# Car_Circuitry.net
KiCad netlist of a schematic drawn in Altium Designer
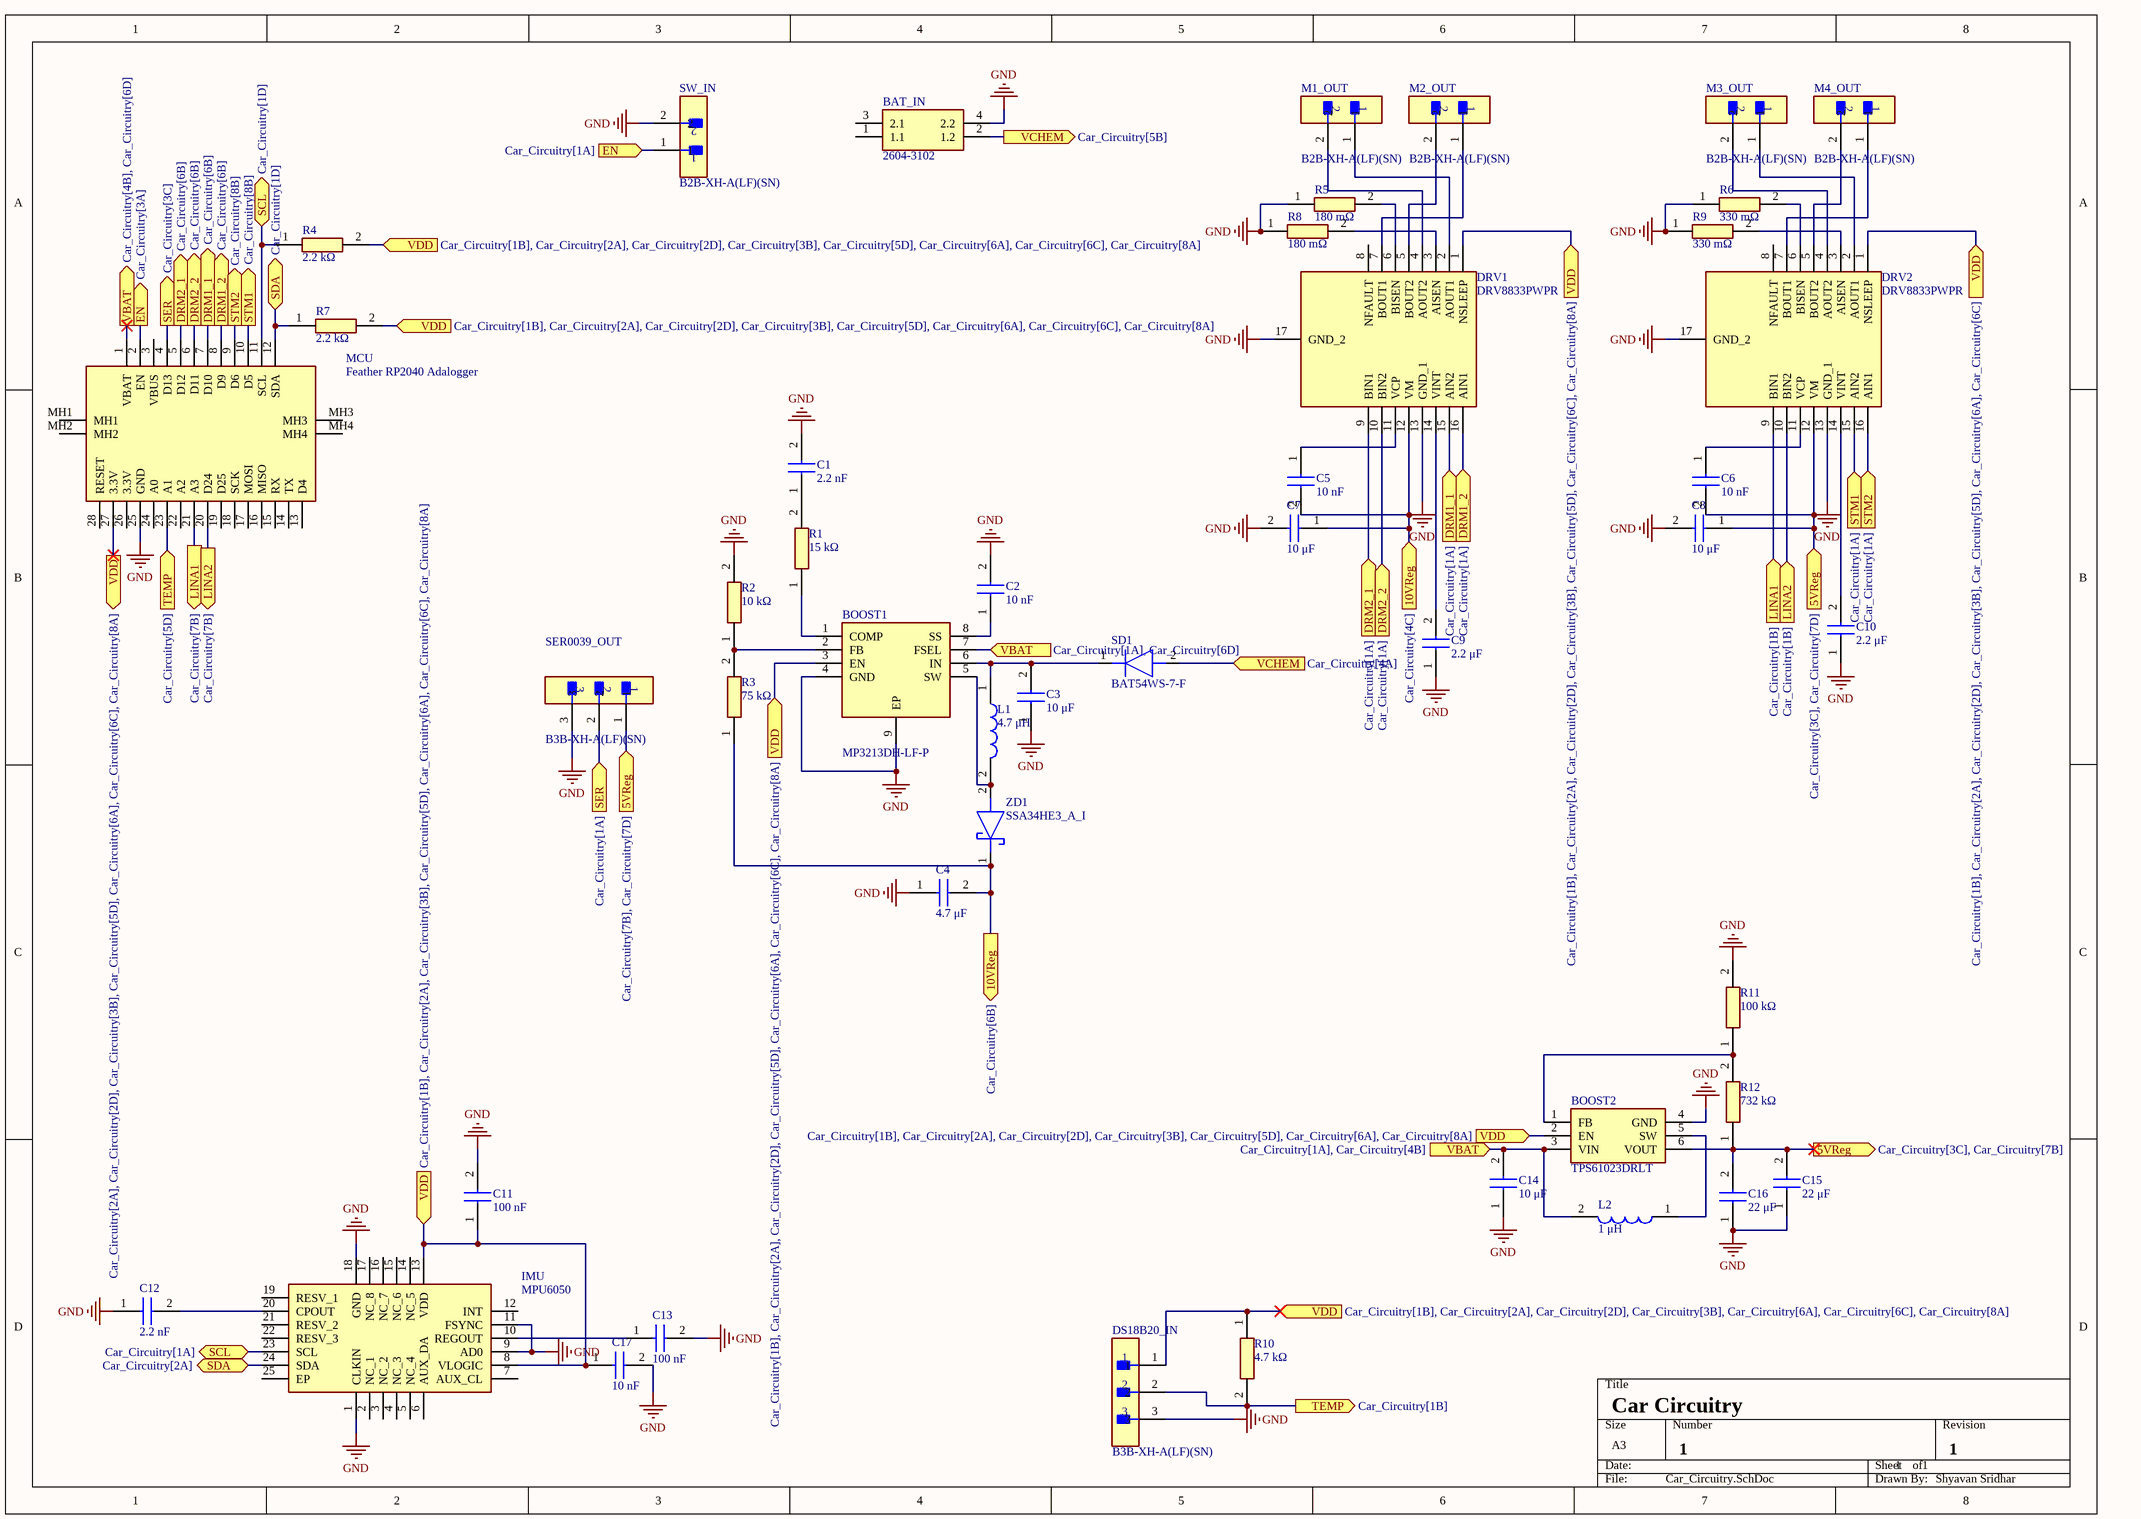
[diagram p0: Car_Circuitry.SchDoc]

(export (version "E")
  (design (tool "Eeschema 10.0.6"))
  (components
    (comp (ref "BAT_IN")
      (value "2604-3102")
      (footprint "SamacSys:26043102")
      (description "Connector")
      (libsource (lib "*") (part "2604-3102"))
    )
    (comp (ref "BOOST1")
      (value "MP3213DH-LF-P")
      (footprint "SamacSys:SOP65P490X110-9N")
      (description "Integrated Circuit")
      (fields (field (name "MOUSER PART NUMBER") "946-MP3213DHLFP"))
      (libsource (lib "*") (part "MP3213DH-LF-P"))
    )
    (comp (ref "BOOST2")
      (value "TPS61023DRLT")
      (footprint "SamacSys:SOTFL50P160X60-6N")
      (description "Integrated Circuit")
      (fields (field (name "MOUSER PART NUMBER") "595-TPS61023DRLT"))
      (libsource (lib "*") (part "TPS61023DRLT"))
    )
    (comp (ref "C1")
      (value "2.2 nF")
      (footprint "SamacSys:CAPC2012X75N")
      (description "Capacitor")
      (fields (field (name "MANUFACTURER_PART_NUMBER") "CL21B222KBANNNC"))
      (libsource (lib "*") (part "CL21B222KBANNNC"))
    )
    (comp (ref "C2")
      (value "10 nF")
      (footprint "SamacSys:CAPC2012X75N")
      (description "Capacitor")
      (fields
        (field (name "MANUFACTURER_PART_NUMBER") "CL21B103KBANNNC")
        (field (name "MOUSER PART NUMBER") "187-CL21B103KBANNNC")
      )
      (libsource (lib "*") (part "CL21B103KBANNNC"))
    )
    (comp (ref "C3")
      (value "10 μF")
      (footprint "SamacSys:CAPC2012X140N")
      (description "Capacitor")
      (fields
        (field (name "MANUFACTURER_PART_NUMBER") "CL21B106KOQNNNE")
        (field (name "MOUSER PART NUMBER") "187-CL21B106KOQNNNE")
      )
      (libsource (lib "*") (part "CL21B106KOQNNNE"))
    )
    (comp (ref "C4")
      (value "4.7 μF")
      (footprint "SamacSys:CAPC2012X135N")
      (description "Capacitor")
      (fields
        (field (name "MANUFACTURER_PART_NUMBER") "CL21B475KOFNNNE")
        (field (name "MOUSER PART NUMBER") "187-CL21B475KOFNNNE")
      )
      (libsource (lib "*") (part "CL21B475KOFNNNE"))
    )
    (comp (ref "C5")
      (value "10 nF")
      (footprint "SamacSys:CAPC2012X75N")
      (description "Capacitor")
      (fields
        (field (name "MANUFACTURER_PART_NUMBER") "CL21B103KBANNNC")
        (field (name "MOUSER PART NUMBER") "187-CL21B103KBANNNC")
      )
      (libsource (lib "*") (part "CL21B103KBANNNC"))
    )
    (comp (ref "C6")
      (value "10 nF")
      (footprint "SamacSys:CAPC2012X75N")
      (description "Capacitor")
      (fields
        (field (name "MANUFACTURER_PART_NUMBER") "CL21B103KBANNNC")
        (field (name "MOUSER PART NUMBER") "187-CL21B103KBANNNC")
      )
      (libsource (lib "*") (part "CL21B103KBANNNC"))
    )
    (comp (ref "C7")
      (value "10 μF")
      (footprint "SamacSys:CAPC2012X140N")
      (description "Capacitor")
      (fields
        (field (name "MANUFACTURER_PART_NUMBER") "CL21B106KOQNNNE")
        (field (name "MOUSER PART NUMBER") "187-CL21B106KOQNNNE")
      )
      (libsource (lib "*") (part "CL21B106KOQNNNE"))
    )
    (comp (ref "C8")
      (value "10 μF")
      (footprint "SamacSys:CAPC2012X140N")
      (description "Capacitor")
      (fields
        (field (name "MANUFACTURER_PART_NUMBER") "CL21B106KOQNNNE")
        (field (name "MOUSER PART NUMBER") "187-CL21B106KOQNNNE")
      )
      (libsource (lib "*") (part "CL21B106KOQNNNE"))
    )
    (comp (ref "C9")
      (value "2.2 μF")
      (footprint "SamacSys:CAPC2012X135N")
      (description "Capacitor")
      (fields (field (name "MANUFACTURER_PART_NUMBER") "CL21B225KAFNNWE"))
      (libsource (lib "*") (part "CL21B225KAFNNWE"))
    )
    (comp (ref "C10")
      (value "2.2 μF")
      (footprint "SamacSys:CAPC2012X135N")
      (description "Capacitor")
      (fields (field (name "MANUFACTURER_PART_NUMBER") "CL21B225KAFNNWE"))
      (libsource (lib "*") (part "CL21B225KAFNNWE"))
    )
    (comp (ref "C11")
      (value "100 nF")
      (footprint "SamacSys:CAPC2012X95N")
      (description "Capacitor")
      (fields
        (field (name "MANUFACTURER_PART_NUMBER") "CL21B104KBCNNNC")
        (field (name "MOUSER PART NUMBER") "187-CL21B104KBCNNNC")
      )
      (libsource (lib "*") (part "CL21B104KBCNNNC"))
    )
    (comp (ref "C12")
      (value "2.2 nF")
      (footprint "SamacSys:CAPC2012X75N")
      (description "Capacitor")
      (fields (field (name "MANUFACTURER_PART_NUMBER") "CL21B222KBANNNC"))
      (libsource (lib "*") (part "CL21B222KBANNNC"))
    )
    (comp (ref "C13")
      (value "100 nF")
      (footprint "SamacSys:CAPC2012X95N")
      (description "Capacitor")
      (fields
        (field (name "MANUFACTURER_PART_NUMBER") "CL21B104KBCNNNC")
        (field (name "MOUSER PART NUMBER") "187-CL21B104KBCNNNC")
      )
      (libsource (lib "*") (part "CL21B104KBCNNNC"))
    )
    (comp (ref "C14")
      (value "10 μF")
      (footprint "SamacSys:CAPC2012X140N")
      (description "Capacitor")
      (fields
        (field (name "MANUFACTURER_PART_NUMBER") "CL21B106KOQNNNE")
        (field (name "MOUSER PART NUMBER") "187-CL21B106KOQNNNE")
      )
      (libsource (lib "*") (part "CL21B106KOQNNNE"))
    )
    (comp (ref "C15")
      (value "22 μF")
      (footprint "SamacSys:CAPC3216X180N")
      (description "Capacitor")
      (fields
        (field (name "MANUFACTURER_PART_NUMBER") "CL31B226KPHNNNE")
        (field (name "MOUSER PART NUMBER") "187-CL31B226KPHNNNE")
      )
      (libsource (lib "*") (part "CL31B226KPHNNNE"))
    )
    (comp (ref "C16")
      (value "22 μF")
      (footprint "SamacSys:CAPC3216X180N")
      (description "Capacitor")
      (fields
        (field (name "MANUFACTURER_PART_NUMBER") "CL31B226KPHNNNE")
        (field (name "MOUSER PART NUMBER") "187-CL31B226KPHNNNE")
      )
      (libsource (lib "*") (part "CL31B226KPHNNNE"))
    )
    (comp (ref "C17")
      (value "10 nF")
      (footprint "SamacSys:CAPC2012X75N")
      (description "Capacitor")
      (fields
        (field (name "MANUFACTURER_PART_NUMBER") "CL21B103KBANNNC")
        (field (name "MOUSER PART NUMBER") "187-CL21B103KBANNNC")
      )
      (libsource (lib "*") (part "CL21B103KBANNNC"))
    )
    (comp (ref "DRV1")
      (value "DRV8833PWPR")
      (footprint "SamacSys:SOP65P640X120-17N")
      (description "Integrated Circuit")
      (fields
        (field (name "MANUFACTURER_PART_NUMBER") "DRV8833PWP")
        (field (name "MOUSER PART NUMBER") "595-DRV8833PWP")
      )
      (libsource (lib "*") (part "DRV8833PWP"))
    )
    (comp (ref "DRV2")
      (value "DRV8833PWPR")
      (footprint "SamacSys:SOP65P640X120-17N")
      (description "Integrated Circuit")
      (fields
        (field (name "MANUFACTURER_PART_NUMBER") "DRV8833PWP")
        (field (name "MOUSER PART NUMBER") "595-DRV8833PWP")
      )
      (libsource (lib "*") (part "DRV8833PWP"))
    )
    (comp (ref "DS18B20_IN")
      (value "B3B-XH-A(LF)(SN)")
      (footprint "FP-B3B-XH-A_LF_SN-MFG")
      (description "CONN HEADER VERT 3POS 2.5MM")
      (libsource (lib "Altium Content Vault") (part "0d3f023dd272f625e17a2be33dea85f"))
    )
    (comp (ref "IMU")
      (value "MPU6050")
      (footprint "SamacSys:MPU6050")
      (description "IMU")
      (libsource (lib "*") (part "MPU6050"))
    )
    (comp (ref "L1")
      (value "4.7 μH")
      (footprint "SamacSys:CDRH8D43NP4R7NC")
      (description "Inductor")
      (fields
        (field (name "MANUFACTURER_PART_NUMBER") "CDRH8D43NP-4R7NC")
        (field (name "MOUSER PART NUMBER") "851-CDRH8D43NP-4R7NC")
      )
      (libsource (lib "*") (part "CDRH8D43NP-4R7NC"))
    )
    (comp (ref "L2")
      (value "1 μH")
      (footprint "SamacSys:74438357010")
      (description "Inductor")
      (fields
        (field (name "MANUFACTURER_PART_NUMBER") "74438357010")
        (field (name "MOUSER PART NUMBER") "710-74438357010")
      )
      (libsource (lib "*") (part "74438357010"))
    )
    (comp (ref "M1_OUT")
      (value "B2B-XH-A(LF)(SN)")
      (footprint "FP-B2B-XH-A_LF_SN-MFG")
      (description "CONN HEADER VERT 2POS 2.5MM")
      (libsource (lib "Altium Content Vault") (part "3bc925449376181038e59eaffc5286c"))
    )
    (comp (ref "M2_OUT")
      (value "B2B-XH-A(LF)(SN)")
      (footprint "FP-B2B-XH-A_LF_SN-MFG")
      (description "CONN HEADER VERT 2POS 2.5MM")
      (libsource (lib "Altium Content Vault") (part "3bc925449376181038e59eaffc5286c"))
    )
    (comp (ref "M3_OUT")
      (value "B2B-XH-A(LF)(SN)")
      (footprint "FP-B2B-XH-A_LF_SN-MFG")
      (description "CONN HEADER VERT 2POS 2.5MM")
      (libsource (lib "Altium Content Vault") (part "3bc925449376181038e59eaffc5286c"))
    )
    (comp (ref "M4_OUT")
      (value "B2B-XH-A(LF)(SN)")
      (footprint "FP-B2B-XH-A_LF_SN-MFG")
      (description "CONN HEADER VERT 2POS 2.5MM")
      (libsource (lib "Altium Content Vault") (part "3bc925449376181038e59eaffc5286c"))
    )
    (comp (ref "MCU")
      (value "Feather RP2040 Adalogger")
      (footprint "SamacSys:2796")
      (description "Adafruit Microcontroller")
      (fields (field (name "MANUFACTURER_PART_NUMBER") "2796") (field (name "MOUSER PART NUMBER") "485-2796"))
      (libsource (lib "*") (part "2796"))
    )
    (comp (ref "R1")
      (value "15 kΩ")
      (footprint "SamacSys:RESC3216X70N")
      (description "Resistor")
      (fields (field (name "MANUFACTURER_PART_NUMBER") "RMCF1206FT15K0"))
      (libsource (lib "*") (part "RMCF1206FT15K0"))
    )
    (comp (ref "R2")
      (value "10 kΩ")
      (footprint "SamacSys:RESC3216X70N")
      (description "Resistor")
      (fields
        (field (name "MANUFACTURER_PART_NUMBER") "RMCF1206FT10K0")
        (field (name "MOUSER PART NUMBER") "708-RMCF1206FT10K0")
      )
      (libsource (lib "*") (part "RMCF1206FT10K0"))
    )
    (comp (ref "R3")
      (value "75 kΩ")
      (footprint "SamacSys:RESC3116X65N")
      (description "Resistor")
      (fields
        (field (name "MANUFACTURER_PART_NUMBER") "RC1206FR-0775KL")
        (field (name "MOUSER PART NUMBER") "603-RC1206FR-0775KL")
      )
      (libsource (lib "*") (part "RC1206FR-0775KL"))
    )
    (comp (ref "R4")
      (value "2.2 kΩ")
      (footprint "SamacSys:RESAD1042W49L330D178")
      (description "Resistor")
      (fields (field (name "MANUFACTURER_PART_NUMBER") "RNMF14FTC2K20"))
      (libsource (lib "*") (part "RNMF14FTC2K20"))
    )
    (comp (ref "R5")
      (value "180 mΩ")
      (footprint "SamacSys:ERJ6_B_BW_R_LW_CW_D")
      (description "Resistor")
      (fields
        (field (name "MANUFACTURER_PART_NUMBER") "ERJ-6DSFR18V")
        (field (name "MOUSER PART NUMBER") "667-ERJ-6DSFR18V")
      )
      (libsource (lib "*") (part "ERJ-6DSFR18V"))
    )
    (comp (ref "R6")
      (value "330 mΩ")
      (footprint "SamacSys:ERJ6_B_BW_R_LW_CW_D")
      (description "Resistor")
      (fields
        (field (name "MANUFACTURER_PART_NUMBER") "ERJ-6DQFR33V")
        (field (name "MOUSER PART NUMBER") "667-ERJ-6DQFR33V")
      )
      (libsource (lib "*") (part "ERJ-6DQFR33V"))
    )
    (comp (ref "R7")
      (value "2.2 kΩ")
      (footprint "SamacSys:RESAD1042W49L330D178")
      (description "Resistor")
      (fields (field (name "MANUFACTURER_PART_NUMBER") "RNMF14FTC2K20"))
      (libsource (lib "*") (part "RNMF14FTC2K20"))
    )
    (comp (ref "R8")
      (value "180 mΩ")
      (footprint "SamacSys:ERJ6_B_BW_R_LW_CW_D")
      (description "Resistor")
      (fields
        (field (name "MANUFACTURER_PART_NUMBER") "ERJ-6DSFR18V")
        (field (name "MOUSER PART NUMBER") "667-ERJ-6DSFR18V")
      )
      (libsource (lib "*") (part "ERJ-6DSFR18V"))
    )
    (comp (ref "R9")
      (value "330 mΩ")
      (footprint "SamacSys:ERJ6_B_BW_R_LW_CW_D")
      (description "Resistor")
      (fields
        (field (name "MANUFACTURER_PART_NUMBER") "ERJ-6DQFR33V")
        (field (name "MOUSER PART NUMBER") "667-ERJ-6DQFR33V")
      )
      (libsource (lib "*") (part "ERJ-6DQFR33V"))
    )
    (comp (ref "R10")
      (value "4.7 kΩ")
      (footprint "SamacSys:RESAD1530W60L610D230")
      (description "Resistor")
      (fields
        (field (name "MANUFACTURER_PART_NUMBER") "CF1/4C472J")
        (field (name "MOUSER PART NUMBER") "660-CF1/4C472J")
      )
      (libsource (lib "*") (part "CF1_4C472J"))
    )
    (comp (ref "R11")
      (value "100 kΩ")
      (footprint "SamacSys:ERJ8ENF1000V")
      (description "Resistor")
      (fields
        (field (name "MANUFACTURER_PART_NUMBER") "ERJ-8ENF1003V")
        (field (name "MOUSER PART NUMBER") "667-ERJ-8ENF1003V")
      )
      (libsource (lib "*") (part "ERJ-8ENF1003V"))
    )
    (comp (ref "R12")
      (value "732 kΩ")
      (footprint "SamacSys:ERJ8ENF1000V")
      (description "Resistor")
      (fields
        (field (name "MANUFACTURER_PART_NUMBER") "ERJ-8ENF7323V")
        (field (name "MOUSER PART NUMBER") "667-ERJ-8ENF7323V")
      )
      (libsource (lib "*") (part "ERJ-8ENF7323V"))
    )
    (comp (ref "SD1")
      (value "BAT54WS-7-F")
      (footprint "SamacSys:SOD2513X120N")
      (description "Diode")
      (fields (field (name "MOUSER PART NUMBER") "621-BAT54WS-F"))
      (libsource (lib "*") (part "BAT54WS-7-F"))
    )
    (comp (ref "SER0039_OUT")
      (value "B3B-XH-A(LF)(SN)")
      (footprint "FP-B3B-XH-A_LF_SN-MFG")
      (description "CONN HEADER VERT 3POS 2.5MM")
      (libsource (lib "") (part "0d3f023dd272f625e17a2be33dea85f_1"))
    )
    (comp (ref "SW_IN")
      (value "B2B-XH-A(LF)(SN)")
      (footprint "FP-B2B-XH-A_LF_SN-MFG")
      (description "CONN HEADER VERT 2POS 2.5MM")
      (libsource (lib "") (part "3bc925449376181038e59eaffc5286c_1"))
    )
    (comp (ref "ZD1")
      (value "SSA34HE3_A_I")
      (footprint "SamacSys:DIONM5127X229N")
      (description "Schottky Diode")
      (fields
        (field (name "MANUFACTURER_PART_NUMBER") "SSA34HE3_A/I")
        (field (name "MOUSER PART NUMBER") "78-SSA34HE3_A/I")
      )
      (libsource (lib "*") (part "SSA34HE3_A_I"))
    )
  )
  (nets
    (net (code "1") (name "/5VReg") (class "Default")
      (node (ref "BOOST2") (pin "6") (pinfunction "VOUT_6") (pintype "passive"))
      (node (ref "C15") (pin "2") (pinfunction "2_2") (pintype "passive"))
      (node (ref "C16") (pin "2") (pinfunction "2_2") (pintype "passive"))
      (node (ref "C6") (pin "2") (pinfunction "2_2") (pintype "passive"))
      (node (ref "C8") (pin "1") (pinfunction "1_1") (pintype "passive"))
      (node (ref "DRV2") (pin "12") (pinfunction "VM_12") (pintype "passive"))
      (node (ref "R12") (pin "1") (pinfunction "1_1") (pintype "passive"))
      (node (ref "SER0039_OUT") (pin "1") (pinfunction "1_1") (pintype "passive"))
    )
    (net (code "2") (name "/10VReg") (class "Default")
      (node (ref "C4") (pin "2") (pinfunction "2_2") (pintype "passive"))
      (node (ref "C5") (pin "2") (pinfunction "2_2") (pintype "passive"))
      (node (ref "C7") (pin "1") (pinfunction "1_1") (pintype "passive"))
      (node (ref "DRV1") (pin "12") (pinfunction "VM_12") (pintype "passive"))
      (node (ref "R3") (pin "1") (pinfunction "1_1") (pintype "passive"))
      (node (ref "ZD1") (pin "1") (pinfunction "K_1") (pintype "passive"))
    )
    (net (code "3") (name "/DRM1_1") (class "Default")
      (node (ref "DRV1") (pin "15") (pinfunction "AIN2_15") (pintype "passive"))
      (node (ref "MCU") (pin "7") (pinfunction "D10_7") (pintype "passive"))
    )
    (net (code "4") (name "/DRM1_2") (class "Default")
      (node (ref "DRV1") (pin "16") (pinfunction "AIN1_16") (pintype "passive"))
      (node (ref "MCU") (pin "8") (pinfunction "D9_8") (pintype "passive"))
    )
    (net (code "5") (name "/DRM2_1") (class "Default")
      (node (ref "DRV1") (pin "9") (pinfunction "BIN1_9") (pintype "passive"))
      (node (ref "MCU") (pin "5") (pinfunction "D12_5") (pintype "passive"))
    )
    (net (code "6") (name "/DRM2_2") (class "Default")
      (node (ref "DRV1") (pin "10") (pinfunction "BIN2_10") (pintype "passive"))
      (node (ref "MCU") (pin "6") (pinfunction "D11_6") (pintype "passive"))
    )
    (net (code "7") (name "/EN") (class "Default")
      (node (ref "MCU") (pin "2") (pinfunction "EN_2") (pintype "passive"))
      (node (ref "SW_IN") (pin "1") (pinfunction "1_1") (pintype "passive"))
    )
    (net (code "8") (name "/LINA1") (class "Default")
      (node (ref "DRV2") (pin "9") (pinfunction "BIN1_9") (pintype "passive"))
      (node (ref "MCU") (pin "21") (pinfunction "A3_21") (pintype "passive"))
    )
    (net (code "9") (name "/LINA2") (class "Default")
      (node (ref "DRV2") (pin "10") (pinfunction "BIN2_10") (pintype "passive"))
      (node (ref "MCU") (pin "20") (pinfunction "D24_20") (pintype "passive"))
    )
    (net (code "10") (name "/SCL") (class "Default")
      (node (ref "IMU") (pin "23") (pinfunction "SCL_23") (pintype "passive"))
      (node (ref "MCU") (pin "11") (pinfunction "SCL_11") (pintype "passive"))
      (node (ref "R4") (pin "1") (pinfunction "1_1") (pintype "passive"))
    )
    (net (code "11") (name "/SDA") (class "Default")
      (node (ref "IMU") (pin "24") (pinfunction "SDA_24") (pintype "passive"))
      (node (ref "MCU") (pin "12") (pinfunction "SDA_12") (pintype "passive"))
      (node (ref "R7") (pin "1") (pinfunction "1_1") (pintype "passive"))
    )
    (net (code "12") (name "/SER") (class "Default")
      (node (ref "MCU") (pin "4") (pinfunction "D13_4") (pintype "passive"))
      (node (ref "SER0039_OUT") (pin "2") (pinfunction "2_2") (pintype "passive"))
    )
    (net (code "13") (name "/STM1") (class "Default")
      (node (ref "DRV2") (pin "15") (pinfunction "AIN2_15") (pintype "passive"))
      (node (ref "MCU") (pin "10") (pinfunction "D5_10") (pintype "passive"))
    )
    (net (code "14") (name "/STM2") (class "Default")
      (node (ref "DRV2") (pin "16") (pinfunction "AIN1_16") (pintype "passive"))
      (node (ref "MCU") (pin "9") (pinfunction "D6_9") (pintype "passive"))
    )
    (net (code "15") (name "/TEMP") (class "Default")
      (node (ref "DS18B20_IN") (pin "2") (pinfunction "2_2") (pintype "passive"))
      (node (ref "MCU") (pin "23") (pinfunction "A1_23") (pintype "passive"))
      (node (ref "R10") (pin "2") (pinfunction "2_2") (pintype "passive"))
    )
    (net (code "16") (name "/VBAT") (class "Default")
      (node (ref "BOOST1") (pin "7") (pinfunction "FSEL_7") (pintype "passive"))
      (node (ref "BOOST2") (pin "3") (pinfunction "VIN_3") (pintype "passive"))
      (node (ref "C14") (pin "2") (pinfunction "2_2") (pintype "passive"))
      (node (ref "L2") (pin "2") (pinfunction "2_2") (pintype "passive"))
      (node (ref "MCU") (pin "1") (pinfunction "VBAT_1") (pintype "passive"))
    )
    (net (code "17") (name "/VCHEM") (class "Default")
      (node (ref "BAT_IN") (pin "2") (pinfunction "1.2_2") (pintype "passive"))
      (node (ref "SD1") (pin "2") (pinfunction "A_2") (pintype "passive"))
    )
    (net (code "18") (name "/VDD") (class "Default")
      (node (ref "BOOST1") (pin "3") (pinfunction "EN_3") (pintype "passive"))
      (node (ref "BOOST2") (pin "2") (pinfunction "EN_2") (pintype "passive"))
      (node (ref "C11") (pin "1") (pinfunction "1_1") (pintype "passive"))
      (node (ref "C17") (pin "1") (pinfunction "1_1") (pintype "passive"))
      (node (ref "DRV1") (pin "1") (pinfunction "NSLEEP_1") (pintype "passive"))
      (node (ref "DRV2") (pin "1") (pinfunction "NSLEEP_1") (pintype "passive"))
      (node (ref "DS18B20_IN") (pin "1") (pinfunction "1_1") (pintype "passive"))
      (node (ref "IMU") (pin "13") (pinfunction "VDD_13") (pintype "passive"))
      (node (ref "IMU") (pin "8") (pinfunction "VLOGIC_8") (pintype "passive"))
      (node (ref "MCU") (pin "27") (pinfunction "3.3V_27") (pintype "passive"))
      (node (ref "R10") (pin "1") (pinfunction "1_1") (pintype "passive"))
      (node (ref "R4") (pin "2") (pinfunction "2_2") (pintype "passive"))
      (node (ref "R7") (pin "2") (pinfunction "2_2") (pintype "passive"))
    )
    (net (code "19") (name "GND") (class "Default")
      (node (ref "BAT_IN") (pin "4") (pinfunction "2.2_4") (pintype "passive"))
      (node (ref "BOOST1") (pin "4") (pinfunction "GND_4") (pintype "passive"))
      (node (ref "BOOST1") (pin "9") (pinfunction "EP_9") (pintype "passive"))
      (node (ref "BOOST2") (pin "4") (pinfunction "GND_4") (pintype "passive"))
      (node (ref "C1") (pin "2") (pinfunction "2_2") (pintype "passive"))
      (node (ref "C10") (pin "1") (pinfunction "1_1") (pintype "passive"))
      (node (ref "C11") (pin "2") (pinfunction "2_2") (pintype "passive"))
      (node (ref "C12") (pin "1") (pinfunction "1_1") (pintype "passive"))
      (node (ref "C13") (pin "2") (pinfunction "2_2") (pintype "passive"))
      (node (ref "C14") (pin "1") (pinfunction "1_1") (pintype "passive"))
      (node (ref "C15") (pin "1") (pinfunction "1_1") (pintype "passive"))
      (node (ref "C16") (pin "1") (pinfunction "1_1") (pintype "passive"))
      (node (ref "C17") (pin "2") (pinfunction "2_2") (pintype "passive"))
      (node (ref "C2") (pin "2") (pinfunction "2_2") (pintype "passive"))
      (node (ref "C3") (pin "1") (pinfunction "1_1") (pintype "passive"))
      (node (ref "C4") (pin "1") (pinfunction "1_1") (pintype "passive"))
      (node (ref "C7") (pin "2") (pinfunction "2_2") (pintype "passive"))
      (node (ref "C8") (pin "2") (pinfunction "2_2") (pintype "passive"))
      (node (ref "C9") (pin "1") (pinfunction "1_1") (pintype "passive"))
      (node (ref "DRV1") (pin "13") (pinfunction "GND_1_13") (pintype "passive"))
      (node (ref "DRV1") (pin "17") (pinfunction "GND_2_17") (pintype "passive"))
      (node (ref "DRV2") (pin "13") (pinfunction "GND_1_13") (pintype "passive"))
      (node (ref "DRV2") (pin "17") (pinfunction "GND_2_17") (pintype "passive"))
      (node (ref "DS18B20_IN") (pin "3") (pinfunction "3_3") (pintype "passive"))
      (node (ref "IMU") (pin "1") (pinfunction "CLKIN_1") (pintype "passive"))
      (node (ref "IMU") (pin "11") (pinfunction "FSYNC_11") (pintype "passive"))
      (node (ref "IMU") (pin "18") (pinfunction "GND_18") (pintype "passive"))
      (node (ref "IMU") (pin "9") (pinfunction "AD0_9") (pintype "passive"))
      (node (ref "MCU") (pin "25") (pinfunction "GND_25") (pintype "passive"))
      (node (ref "R11") (pin "2") (pinfunction "2_2") (pintype "passive"))
      (node (ref "R2") (pin "2") (pinfunction "2_2") (pintype "passive"))
      (node (ref "R5") (pin "1") (pinfunction "1_1") (pintype "passive"))
      (node (ref "R6") (pin "1") (pinfunction "1_1") (pintype "passive"))
      (node (ref "R8") (pin "1") (pinfunction "1_1") (pintype "passive"))
      (node (ref "R9") (pin "1") (pinfunction "1_1") (pintype "passive"))
      (node (ref "SER0039_OUT") (pin "3") (pinfunction "3_3") (pintype "passive"))
      (node (ref "SW_IN") (pin "2") (pinfunction "2_2") (pintype "passive"))
    )
    (net (code "20") (name "Net-(BOOST1-COMP)") (class "Default")
      (node (ref "BOOST1") (pin "1") (pinfunction "COMP_1") (pintype "passive"))
      (node (ref "R1") (pin "1") (pinfunction "1_1") (pintype "passive"))
    )
    (net (code "21") (name "Net-(BOOST1-FB)") (class "Default")
      (node (ref "BOOST1") (pin "2") (pinfunction "FB_2") (pintype "passive"))
      (node (ref "R2") (pin "1") (pinfunction "1_1") (pintype "passive"))
      (node (ref "R3") (pin "2") (pinfunction "2_2") (pintype "passive"))
    )
    (net (code "22") (name "Net-(BOOST1-IN)") (class "Default")
      (node (ref "BOOST1") (pin "6") (pinfunction "IN_6") (pintype "passive"))
      (node (ref "C3") (pin "2") (pinfunction "2_2") (pintype "passive"))
      (node (ref "L1") (pin "1") (pinfunction "1_1") (pintype "passive"))
      (node (ref "SD1") (pin "1") (pinfunction "K_1") (pintype "passive"))
    )
    (net (code "23") (name "Net-(BOOST1-SS)") (class "Default")
      (node (ref "BOOST1") (pin "8") (pinfunction "SS_8") (pintype "passive"))
      (node (ref "C2") (pin "1") (pinfunction "1_1") (pintype "passive"))
    )
    (net (code "24") (name "Net-(BOOST1-SW)") (class "Default")
      (node (ref "BOOST1") (pin "5") (pinfunction "SW_5") (pintype "passive"))
      (node (ref "L1") (pin "2") (pinfunction "2_2") (pintype "passive"))
      (node (ref "ZD1") (pin "2") (pinfunction "A_2") (pintype "passive"))
    )
    (net (code "25") (name "Net-(BOOST2-FB)") (class "Default")
      (node (ref "BOOST2") (pin "1") (pinfunction "FB_1") (pintype "passive"))
      (node (ref "R11") (pin "1") (pinfunction "1_1") (pintype "passive"))
      (node (ref "R12") (pin "2") (pinfunction "2_2") (pintype "passive"))
    )
    (net (code "26") (name "Net-(BOOST2-SW)") (class "Default")
      (node (ref "BOOST2") (pin "5") (pinfunction "SW_5") (pintype "passive"))
      (node (ref "L2") (pin "1") (pinfunction "1_1") (pintype "passive"))
    )
    (net (code "27") (name "Net-(C1-Pad1)") (class "Default")
      (node (ref "C1") (pin "1") (pinfunction "1_1") (pintype "passive"))
      (node (ref "R1") (pin "2") (pinfunction "2_2") (pintype "passive"))
    )
    (net (code "28") (name "Net-(DRV1-AISEN)") (class "Default")
      (node (ref "DRV1") (pin "3") (pinfunction "AISEN_3") (pintype "passive"))
      (node (ref "R8") (pin "2") (pinfunction "2_2") (pintype "passive"))
    )
    (net (code "29") (name "Net-(DRV1-AOUT1)") (class "Default")
      (node (ref "DRV1") (pin "2") (pinfunction "AOUT1_2") (pintype "passive"))
      (node (ref "M1_OUT") (pin "1") (pinfunction "1_1") (pintype "passive"))
    )
    (net (code "30") (name "Net-(DRV1-AOUT2)") (class "Default")
      (node (ref "DRV1") (pin "4") (pinfunction "AOUT2_4") (pintype "passive"))
      (node (ref "M1_OUT") (pin "2") (pinfunction "2_2") (pintype "passive"))
    )
    (net (code "31") (name "Net-(DRV1-BISEN)") (class "Default")
      (node (ref "DRV1") (pin "6") (pinfunction "BISEN_6") (pintype "passive"))
      (node (ref "R5") (pin "2") (pinfunction "2_2") (pintype "passive"))
    )
    (net (code "32") (name "Net-(DRV1-BOUT1)") (class "Default")
      (node (ref "DRV1") (pin "7") (pinfunction "BOUT1_7") (pintype "passive"))
      (node (ref "M2_OUT") (pin "1") (pinfunction "1_1") (pintype "passive"))
    )
    (net (code "33") (name "Net-(DRV1-BOUT2)") (class "Default")
      (node (ref "DRV1") (pin "5") (pinfunction "BOUT2_5") (pintype "passive"))
      (node (ref "M2_OUT") (pin "2") (pinfunction "2_2") (pintype "passive"))
    )
    (net (code "34") (name "Net-(DRV1-VCP)") (class "Default")
      (node (ref "C5") (pin "1") (pinfunction "1_1") (pintype "passive"))
      (node (ref "DRV1") (pin "11") (pinfunction "VCP_11") (pintype "passive"))
    )
    (net (code "35") (name "Net-(DRV1-VINT)") (class "Default")
      (node (ref "C9") (pin "2") (pinfunction "2_2") (pintype "passive"))
      (node (ref "DRV1") (pin "14") (pinfunction "VINT_14") (pintype "passive"))
    )
    (net (code "36") (name "Net-(DRV2-AISEN)") (class "Default")
      (node (ref "DRV2") (pin "3") (pinfunction "AISEN_3") (pintype "passive"))
      (node (ref "R9") (pin "2") (pinfunction "2_2") (pintype "passive"))
    )
    (net (code "37") (name "Net-(DRV2-AOUT1)") (class "Default")
      (node (ref "DRV2") (pin "2") (pinfunction "AOUT1_2") (pintype "passive"))
      (node (ref "M3_OUT") (pin "1") (pinfunction "1_1") (pintype "passive"))
    )
    (net (code "38") (name "Net-(DRV2-AOUT2)") (class "Default")
      (node (ref "DRV2") (pin "4") (pinfunction "AOUT2_4") (pintype "passive"))
      (node (ref "M3_OUT") (pin "2") (pinfunction "2_2") (pintype "passive"))
    )
    (net (code "39") (name "Net-(DRV2-BISEN)") (class "Default")
      (node (ref "DRV2") (pin "6") (pinfunction "BISEN_6") (pintype "passive"))
      (node (ref "R6") (pin "2") (pinfunction "2_2") (pintype "passive"))
    )
    (net (code "40") (name "Net-(DRV2-BOUT1)") (class "Default")
      (node (ref "DRV2") (pin "7") (pinfunction "BOUT1_7") (pintype "passive"))
      (node (ref "M4_OUT") (pin "1") (pinfunction "1_1") (pintype "passive"))
    )
    (net (code "41") (name "Net-(DRV2-BOUT2)") (class "Default")
      (node (ref "DRV2") (pin "5") (pinfunction "BOUT2_5") (pintype "passive"))
      (node (ref "M4_OUT") (pin "2") (pinfunction "2_2") (pintype "passive"))
    )
    (net (code "42") (name "Net-(DRV2-VCP)") (class "Default")
      (node (ref "C6") (pin "1") (pinfunction "1_1") (pintype "passive"))
      (node (ref "DRV2") (pin "11") (pinfunction "VCP_11") (pintype "passive"))
    )
    (net (code "43") (name "Net-(DRV2-VINT)") (class "Default")
      (node (ref "C10") (pin "2") (pinfunction "2_2") (pintype "passive"))
      (node (ref "DRV2") (pin "14") (pinfunction "VINT_14") (pintype "passive"))
    )
    (net (code "44") (name "Net-(IMU-CPOUT)") (class "Default")
      (node (ref "C12") (pin "2") (pinfunction "2_2") (pintype "passive"))
      (node (ref "IMU") (pin "20") (pinfunction "CPOUT_20") (pintype "passive"))
    )
    (net (code "45") (name "Net-(IMU-REGOUT)") (class "Default")
      (node (ref "C13") (pin "1") (pinfunction "1_1") (pintype "passive"))
      (node (ref "IMU") (pin "10") (pinfunction "REGOUT_10") (pintype "passive"))
    )
    (net (code "46") (name "unconnected-(BAT_IN-1.1-Pad1)") (class "Default")
      (node (ref "BAT_IN") (pin "1") (pinfunction "1.1_1") (pintype "passive"))
    )
    (net (code "47") (name "unconnected-(BAT_IN-2.1-Pad3)") (class "Default")
      (node (ref "BAT_IN") (pin "3") (pinfunction "2.1_3") (pintype "passive"))
    )
    (net (code "48") (name "unconnected-(DRV1-NFAULT-Pad8)") (class "Default")
      (node (ref "DRV1") (pin "8") (pinfunction "NFAULT_8") (pintype "passive"))
    )
    (net (code "49") (name "unconnected-(DRV2-NFAULT-Pad8)") (class "Default")
      (node (ref "DRV2") (pin "8") (pinfunction "NFAULT_8") (pintype "passive"))
    )
    (net (code "50") (name "unconnected-(IMU-AUX_CL-Pad7)") (class "Default")
      (node (ref "IMU") (pin "7") (pinfunction "AUX_CL_7") (pintype "passive"))
    )
    (net (code "51") (name "unconnected-(IMU-AUX_DA-Pad6)") (class "Default")
      (node (ref "IMU") (pin "6") (pinfunction "AUX_DA_6") (pintype "passive"))
    )
    (net (code "52") (name "unconnected-(IMU-EP-Pad25)") (class "Default")
      (node (ref "IMU") (pin "25") (pinfunction "EP_25") (pintype "passive"))
    )
    (net (code "53") (name "unconnected-(IMU-INT-Pad12)") (class "Default")
      (node (ref "IMU") (pin "12") (pinfunction "INT_12") (pintype "passive"))
    )
    (net (code "54") (name "unconnected-(IMU-NC_1-Pad2)") (class "Default")
      (node (ref "IMU") (pin "2") (pinfunction "NC_1_2") (pintype "passive"))
    )
    (net (code "55") (name "unconnected-(IMU-NC_2-Pad3)") (class "Default")
      (node (ref "IMU") (pin "3") (pinfunction "NC_2_3") (pintype "passive"))
    )
    (net (code "56") (name "unconnected-(IMU-NC_3-Pad4)") (class "Default")
      (node (ref "IMU") (pin "4") (pinfunction "NC_3_4") (pintype "passive"))
    )
    (net (code "57") (name "unconnected-(IMU-NC_4-Pad5)") (class "Default")
      (node (ref "IMU") (pin "5") (pinfunction "NC_4_5") (pintype "passive"))
    )
    (net (code "58") (name "unconnected-(IMU-NC_5-Pad14)") (class "Default")
      (node (ref "IMU") (pin "14") (pinfunction "NC_5_14") (pintype "passive"))
    )
    (net (code "59") (name "unconnected-(IMU-NC_6-Pad15)") (class "Default")
      (node (ref "IMU") (pin "15") (pinfunction "NC_6_15") (pintype "passive"))
    )
    (net (code "60") (name "unconnected-(IMU-NC_7-Pad16)") (class "Default")
      (node (ref "IMU") (pin "16") (pinfunction "NC_7_16") (pintype "passive"))
    )
    (net (code "61") (name "unconnected-(IMU-NC_8-Pad17)") (class "Default")
      (node (ref "IMU") (pin "17") (pinfunction "NC_8_17") (pintype "passive"))
    )
    (net (code "62") (name "unconnected-(IMU-RESV_1-Pad19)") (class "Default")
      (node (ref "IMU") (pin "19") (pinfunction "RESV_1_19") (pintype "passive"))
    )
    (net (code "63") (name "unconnected-(IMU-RESV_2-Pad21)") (class "Default")
      (node (ref "IMU") (pin "21") (pinfunction "RESV_2_21") (pintype "passive"))
    )
    (net (code "64") (name "unconnected-(IMU-RESV_3-Pad22)") (class "Default")
      (node (ref "IMU") (pin "22") (pinfunction "RESV_3_22") (pintype "passive"))
    )
    (net (code "65") (name "unconnected-(MCU-3.3V-Pad26)") (class "Default")
      (node (ref "MCU") (pin "26") (pinfunction "3.3V_26") (pintype "passive"))
    )
    (net (code "66") (name "unconnected-(MCU-A0-Pad24)") (class "Default")
      (node (ref "MCU") (pin "24") (pinfunction "A0_24") (pintype "passive"))
    )
    (net (code "67") (name "unconnected-(MCU-A2-Pad22)") (class "Default")
      (node (ref "MCU") (pin "22") (pinfunction "A2_22") (pintype "passive"))
    )
    (net (code "68") (name "unconnected-(MCU-D4-Pad13)") (class "Default")
      (node (ref "MCU") (pin "13") (pinfunction "D4_13") (pintype "passive"))
    )
    (net (code "69") (name "unconnected-(MCU-D25-Pad19)") (class "Default")
      (node (ref "MCU") (pin "19") (pinfunction "D25_19") (pintype "passive"))
    )
    (net (code "70") (name "unconnected-(MCU-MISO-Pad16)") (class "Default")
      (node (ref "MCU") (pin "16") (pinfunction "MISO_16") (pintype "passive"))
    )
    (net (code "71") (name "unconnected-(MCU-MOSI-Pad17)") (class "Default")
      (node (ref "MCU") (pin "17") (pinfunction "MOSI_17") (pintype "passive"))
    )
    (net (code "72") (name "unconnected-(MCU-PadMH1)") (class "Default")
      (node (ref "MCU") (pin "MH1") (pinfunction "MH1_MH1") (pintype "passive"))
    )
    (net (code "73") (name "unconnected-(MCU-PadMH2)") (class "Default")
      (node (ref "MCU") (pin "MH2") (pinfunction "MH2_MH2") (pintype "passive"))
    )
    (net (code "74") (name "unconnected-(MCU-PadMH3)") (class "Default")
      (node (ref "MCU") (pin "MH3") (pinfunction "MH3_MH3") (pintype "passive"))
    )
    (net (code "75") (name "unconnected-(MCU-PadMH4)") (class "Default")
      (node (ref "MCU") (pin "MH4") (pinfunction "MH4_MH4") (pintype "passive"))
    )
    (net (code "76") (name "unconnected-(MCU-RESET-Pad28)") (class "Default")
      (node (ref "MCU") (pin "28") (pinfunction "RESET_28") (pintype "passive"))
    )
    (net (code "77") (name "unconnected-(MCU-RX-Pad15)") (class "Default")
      (node (ref "MCU") (pin "15") (pinfunction "RX_15") (pintype "passive"))
    )
    (net (code "78") (name "unconnected-(MCU-SCK-Pad18)") (class "Default")
      (node (ref "MCU") (pin "18") (pinfunction "SCK_18") (pintype "passive"))
    )
    (net (code "79") (name "unconnected-(MCU-TX-Pad14)") (class "Default")
      (node (ref "MCU") (pin "14") (pinfunction "TX_14") (pintype "passive"))
    )
    (net (code "80") (name "unconnected-(MCU-VBUS-Pad3)") (class "Default")
      (node (ref "MCU") (pin "3") (pinfunction "VBUS_3") (pintype "passive"))
    )
  )
)
